# 6_-H3_MAIN.net
KiCad netlist of a schematic drawn in Altium Designer
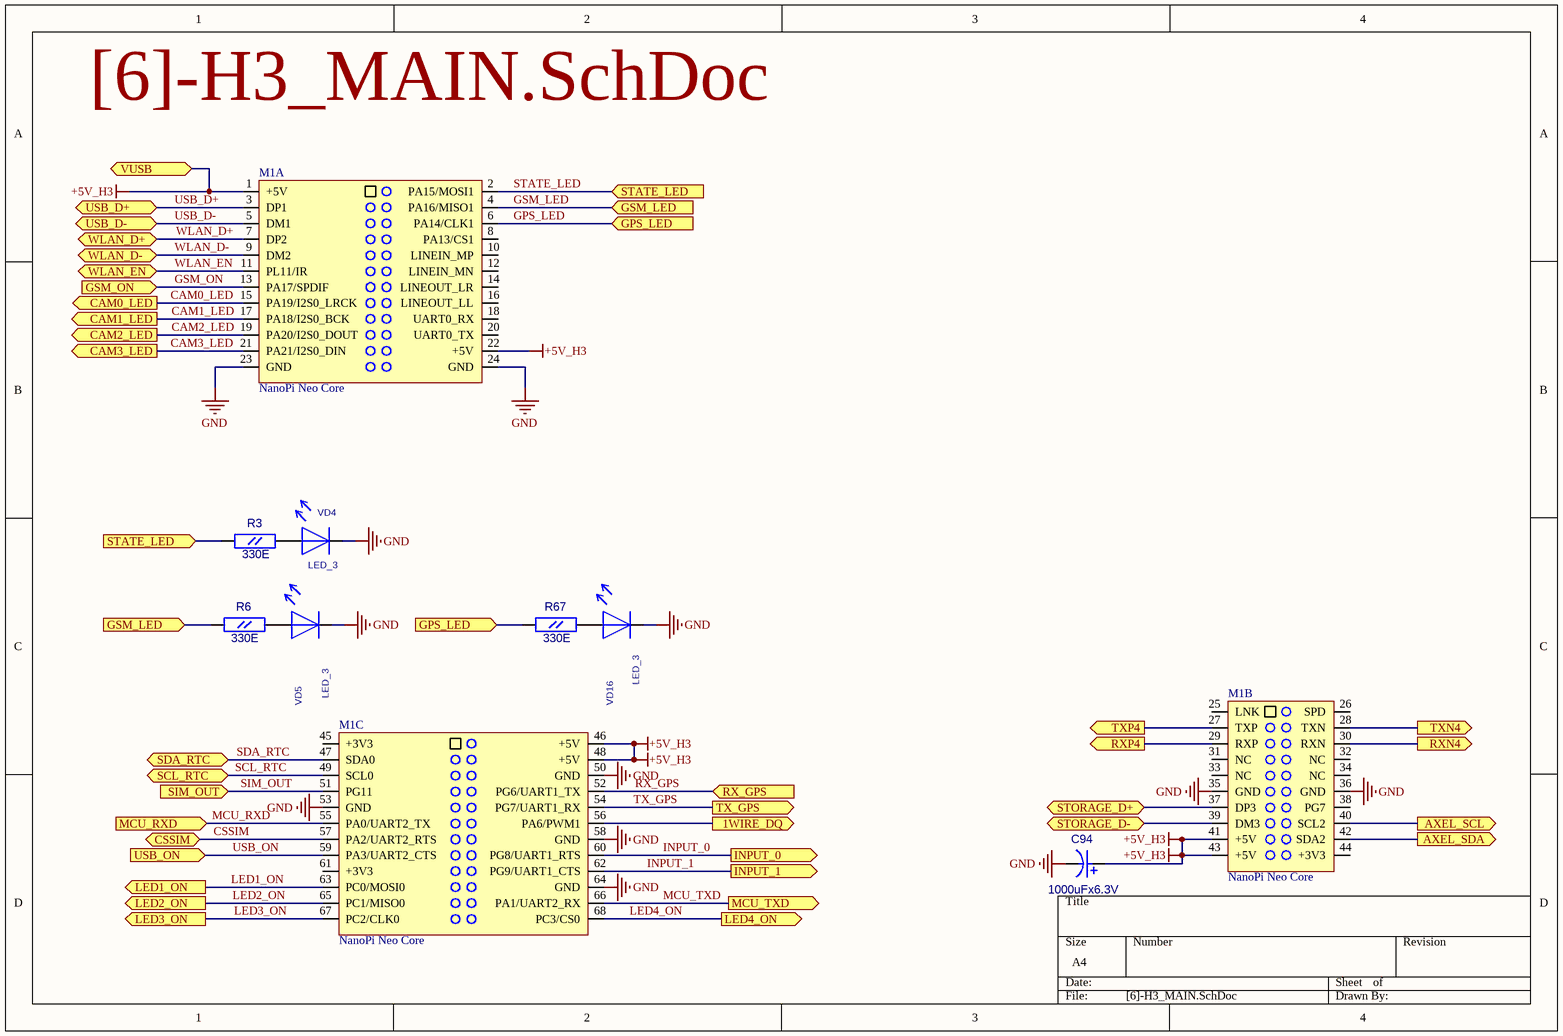
[diagram p0: [6]-H3_MAIN.SchDoc]

(export (version "E")
  (design (tool "Eeschema 10.0.6"))
  (components
    (comp (ref "C94")
      (value "1000uFx6.3V")
      (footprint "CC8X3.5")
      (description "Radial capacitor")
      (libsource (lib "fizik_lib (1)") (part "CAP_8mm"))
    )
    (comp (ref "M1")
      (value "NanoPi Neo Core")
      (footprint "NanoPiNeo_CORE")
      (description "Nano Pi Neo Core Allwinner H3 based embedded module")
      (libsource (lib "") (part "NanoPi Neo Core_1"))
    )
    (comp (ref "R3")
      (value "330E")
      (footprint "RC0603")
      (description "RC0603")
      (libsource (lib "fizik_lib (1)") (part "RC0603"))
    )
    (comp (ref "R6")
      (value "330E")
      (footprint "RC0603")
      (description "RC0603")
      (libsource (lib "fizik_lib (1)") (part "RC0603"))
    )
    (comp (ref "R67")
      (value "330E")
      (footprint "RC0603")
      (description "RC0603")
      (libsource (lib "fizik_lib (1)") (part "RC0603"))
    )
    (comp (ref "VD4") (value "LED_3") (footprint "LED3") (libsource (lib "fizik_lib (1)") (part "LED_3")))
    (comp (ref "VD5") (value "LED_3") (footprint "LED3") (libsource (lib "fizik_lib (1)") (part "LED_3")))
    (comp (ref "VD16") (value "LED_3") (footprint "LED3") (libsource (lib "fizik_lib (1)") (part "LED_3")))
  )
  (nets
    (net (code "1") (name "+5V_H3") (class "Default")
      (node (ref "C94") (pin "1") (pintype "passive"))
      (node (ref "M1") (pin "1") (pinfunction "+5V_1") (pintype "passive"))
      (node (ref "M1") (pin "22") (pinfunction "+5V_22") (pintype "passive"))
      (node (ref "M1") (pin "41") (pinfunction "+5V_41") (pintype "passive"))
      (node (ref "M1") (pin "43") (pinfunction "+5V_43") (pintype "passive"))
      (node (ref "M1") (pin "46") (pinfunction "+5V_46") (pintype "passive"))
      (node (ref "M1") (pin "48") (pinfunction "+5V_48") (pintype "passive"))
    )
    (net (code "2") (name "/1WIRE_DQ") (class "Default")
      (node (ref "M1") (pin "56") (pinfunction "PA6/PWM1_56") (pintype "passive"))
    )
    (net (code "3") (name "/AXEL_SCL") (class "Default")
      (node (ref "M1") (pin "40") (pinfunction "SCL2_40") (pintype "passive"))
    )
    (net (code "4") (name "/AXEL_SDA") (class "Default")
      (node (ref "M1") (pin "42") (pinfunction "SDA2_42") (pintype "passive"))
    )
    (net (code "5") (name "/CAM0_LED") (class "Default")
      (node (ref "M1") (pin "15") (pinfunction "PA19/I2S0_LRCK_15") (pintype "passive"))
    )
    (net (code "6") (name "/CAM1_LED") (class "Default")
      (node (ref "M1") (pin "17") (pinfunction "PA18/I2S0_BCK_17") (pintype "passive"))
    )
    (net (code "7") (name "/CAM2_LED") (class "Default")
      (node (ref "M1") (pin "19") (pinfunction "PA20/I2S0_DOUT_19") (pintype "passive"))
    )
    (net (code "8") (name "/CAM3_LED") (class "Default")
      (node (ref "M1") (pin "21") (pinfunction "PA21/I2S0_DIN_21") (pintype "passive"))
    )
    (net (code "9") (name "/CSSIM") (class "Default")
      (node (ref "M1") (pin "57") (pinfunction "PA2/UART2_RTS_57") (pintype "passive"))
    )
    (net (code "10") (name "/GPS_LED") (class "Default")
      (node (ref "M1") (pin "6") (pinfunction "PA14/CLK1_6") (pintype "passive"))
      (node (ref "R67") (pin "1") (pinfunction "A_1") (pintype "passive"))
    )
    (net (code "11") (name "/GSM_LED") (class "Default")
      (node (ref "M1") (pin "4") (pinfunction "PA16/MISO1_4") (pintype "passive"))
      (node (ref "R6") (pin "1") (pinfunction "A_1") (pintype "passive"))
    )
    (net (code "12") (name "/GSM_ON") (class "Default")
      (node (ref "M1") (pin "13") (pinfunction "PA17/SPDIF_13") (pintype "passive"))
    )
    (net (code "13") (name "/INPUT_0") (class "Default")
      (node (ref "M1") (pin "60") (pinfunction "PG8/UART1_RTS_60") (pintype "passive"))
    )
    (net (code "14") (name "/INPUT_1") (class "Default")
      (node (ref "M1") (pin "62") (pinfunction "PG9/UART1_CTS_62") (pintype "passive"))
    )
    (net (code "15") (name "/LED1_ON") (class "Default")
      (node (ref "M1") (pin "63") (pinfunction "PC0/MOSI0_63") (pintype "passive"))
    )
    (net (code "16") (name "/LED2_ON") (class "Default")
      (node (ref "M1") (pin "65") (pinfunction "PC1/MISO0_65") (pintype "passive"))
    )
    (net (code "17") (name "/LED3_ON") (class "Default")
      (node (ref "M1") (pin "67") (pinfunction "PC2/CLK0_67") (pintype "passive"))
    )
    (net (code "18") (name "/LED4_ON") (class "Default")
      (node (ref "M1") (pin "68") (pinfunction "PC3/CS0_68") (pintype "passive"))
    )
    (net (code "19") (name "/MCU_RXD") (class "Default")
      (node (ref "M1") (pin "55") (pinfunction "PA0/UART2_TX_55") (pintype "passive"))
    )
    (net (code "20") (name "/MCU_TXD") (class "Default")
      (node (ref "M1") (pin "66") (pinfunction "PA1/UART2_RX_66") (pintype "passive"))
    )
    (net (code "21") (name "/RXN4") (class "Default")
      (node (ref "M1") (pin "30") (pinfunction "RXN_30") (pintype "passive"))
    )
    (net (code "22") (name "/RXP4") (class "Default")
      (node (ref "M1") (pin "29") (pinfunction "RXP_29") (pintype "passive"))
    )
    (net (code "23") (name "/RX_GPS") (class "Default")
      (node (ref "M1") (pin "52") (pinfunction "PG6/UART1_TX_52") (pintype "passive"))
    )
    (net (code "24") (name "/SCL_RTC") (class "Default")
      (node (ref "M1") (pin "49") (pinfunction "SCL0_49") (pintype "passive"))
    )
    (net (code "25") (name "/SDA_RTC") (class "Default")
      (node (ref "M1") (pin "47") (pinfunction "SDA0_47") (pintype "passive"))
    )
    (net (code "26") (name "/SIM_OUT") (class "Default")
      (node (ref "M1") (pin "51") (pinfunction "PG11_51") (pintype "passive"))
    )
    (net (code "27") (name "/STATE_LED") (class "Default")
      (node (ref "M1") (pin "2") (pinfunction "PA15/MOSI1_2") (pintype "passive"))
      (node (ref "R3") (pin "1") (pinfunction "A_1") (pintype "passive"))
    )
    (net (code "28") (name "/STORAGE_D+") (class "Default")
      (node (ref "M1") (pin "37") (pinfunction "DP3_37") (pintype "passive"))
    )
    (net (code "29") (name "/STORAGE_D-") (class "Default")
      (node (ref "M1") (pin "39") (pinfunction "DM3_39") (pintype "passive"))
    )
    (net (code "30") (name "/TXN4") (class "Default")
      (node (ref "M1") (pin "28") (pinfunction "TXN_28") (pintype "passive"))
    )
    (net (code "31") (name "/TXP4") (class "Default")
      (node (ref "M1") (pin "27") (pinfunction "TXP_27") (pintype "passive"))
    )
    (net (code "32") (name "/TX_GPS") (class "Default")
      (node (ref "M1") (pin "54") (pinfunction "PG7/UART1_RX_54") (pintype "passive"))
    )
    (net (code "33") (name "/USB_D+") (class "Default")
      (node (ref "M1") (pin "3") (pinfunction "DP1_3") (pintype "passive"))
    )
    (net (code "34") (name "/USB_D-") (class "Default")
      (node (ref "M1") (pin "5") (pinfunction "DM1_5") (pintype "passive"))
    )
    (net (code "35") (name "/USB_ON") (class "Default")
      (node (ref "M1") (pin "59") (pinfunction "PA3/UART2_CTS_59") (pintype "passive"))
    )
    (net (code "36") (name "/WLAN_D+") (class "Default")
      (node (ref "M1") (pin "7") (pinfunction "DP2_7") (pintype "passive"))
    )
    (net (code "37") (name "/WLAN_D-") (class "Default")
      (node (ref "M1") (pin "9") (pinfunction "DM2_9") (pintype "passive"))
    )
    (net (code "38") (name "/WLAN_EN") (class "Default")
      (node (ref "M1") (pin "11") (pinfunction "PL11/IR_11") (pintype "passive"))
    )
    (net (code "39") (name "GND") (class "Default")
      (node (ref "C94") (pin "2") (pintype "passive"))
      (node (ref "M1") (pin "23") (pinfunction "GND_23") (pintype "passive"))
      (node (ref "M1") (pin "24") (pinfunction "GND_24") (pintype "passive"))
      (node (ref "M1") (pin "35") (pinfunction "GND_35") (pintype "passive"))
      (node (ref "M1") (pin "36") (pinfunction "GND_36") (pintype "passive"))
      (node (ref "M1") (pin "50") (pinfunction "GND_50") (pintype "passive"))
      (node (ref "M1") (pin "53") (pinfunction "GND_53") (pintype "passive"))
      (node (ref "M1") (pin "58") (pinfunction "GND_58") (pintype "passive"))
      (node (ref "M1") (pin "64") (pinfunction "GND_64") (pintype "passive"))
      (node (ref "VD16") (pin "1") (pintype "passive"))
      (node (ref "VD4") (pin "1") (pintype "passive"))
      (node (ref "VD5") (pin "1") (pintype "passive"))
    )
    (net (code "40") (name "Net-(R3-B)") (class "Default")
      (node (ref "R3") (pin "2") (pinfunction "B_2") (pintype "passive"))
      (node (ref "VD4") (pin "2") (pintype "passive"))
    )
    (net (code "41") (name "Net-(R6-B)") (class "Default")
      (node (ref "R6") (pin "2") (pinfunction "B_2") (pintype "passive"))
      (node (ref "VD5") (pin "2") (pintype "passive"))
    )
    (net (code "42") (name "Net-(R67-B)") (class "Default")
      (node (ref "R67") (pin "2") (pinfunction "B_2") (pintype "passive"))
      (node (ref "VD16") (pin "2") (pintype "passive"))
    )
    (net (code "43") (name "unconnected-(M1A-LINEIN_MN-Pad12)") (class "Default")
      (node (ref "M1") (pin "12") (pinfunction "LINEIN_MN_12") (pintype "passive"))
    )
    (net (code "44") (name "unconnected-(M1A-LINEIN_MP-Pad10)") (class "Default")
      (node (ref "M1") (pin "10") (pinfunction "LINEIN_MP_10") (pintype "passive"))
    )
    (net (code "45") (name "unconnected-(M1A-LINEOUT_LL-Pad16)") (class "Default")
      (node (ref "M1") (pin "16") (pinfunction "LINEOUT_LL_16") (pintype "passive"))
    )
    (net (code "46") (name "unconnected-(M1A-LINEOUT_LR-Pad14)") (class "Default")
      (node (ref "M1") (pin "14") (pinfunction "LINEOUT_LR_14") (pintype "passive"))
    )
    (net (code "47") (name "unconnected-(M1A-PA13{slash}CS1-Pad8)") (class "Default")
      (node (ref "M1") (pin "8") (pinfunction "PA13/CS1_8") (pintype "passive"))
    )
    (net (code "48") (name "unconnected-(M1A-UART0_RX-Pad18)") (class "Default")
      (node (ref "M1") (pin "18") (pinfunction "UART0_RX_18") (pintype "passive"))
    )
    (net (code "49") (name "unconnected-(M1A-UART0_TX-Pad20)") (class "Default")
      (node (ref "M1") (pin "20") (pinfunction "UART0_TX_20") (pintype "passive"))
    )
    (net (code "50") (name "unconnected-(M1B-+3V3-Pad44)") (class "Default")
      (node (ref "M1") (pin "44") (pinfunction "+3V3_44") (pintype "passive"))
    )
    (net (code "51") (name "unconnected-(M1B-LNK-Pad25)") (class "Default")
      (node (ref "M1") (pin "25") (pinfunction "LNK_25") (pintype "passive"))
    )
    (net (code "52") (name "unconnected-(M1B-NC-Pad31)") (class "Default")
      (node (ref "M1") (pin "31") (pinfunction "NC_31") (pintype "passive"))
    )
    (net (code "53") (name "unconnected-(M1B-NC-Pad32)") (class "Default")
      (node (ref "M1") (pin "32") (pinfunction "NC_32") (pintype "passive"))
    )
    (net (code "54") (name "unconnected-(M1B-NC-Pad33)") (class "Default")
      (node (ref "M1") (pin "33") (pinfunction "NC_33") (pintype "passive"))
    )
    (net (code "55") (name "unconnected-(M1B-NC-Pad34)") (class "Default")
      (node (ref "M1") (pin "34") (pinfunction "NC_34") (pintype "passive"))
    )
    (net (code "56") (name "unconnected-(M1B-PG7-Pad38)") (class "Default")
      (node (ref "M1") (pin "38") (pinfunction "PG7_38") (pintype "passive"))
    )
    (net (code "57") (name "unconnected-(M1B-SPD-Pad26)") (class "Default")
      (node (ref "M1") (pin "26") (pinfunction "SPD_26") (pintype "passive"))
    )
    (net (code "58") (name "unconnected-(M1C-+3V3-Pad45)") (class "Default")
      (node (ref "M1") (pin "45") (pinfunction "+3V3_45") (pintype "passive"))
    )
    (net (code "59") (name "unconnected-(M1C-+3V3-Pad61)") (class "Default")
      (node (ref "M1") (pin "61") (pinfunction "+3V3_61") (pintype "passive"))
    )
  )
)
